# 08_PL_ETH_1.net
KiCad netlist of a schematic drawn in Altium Designer
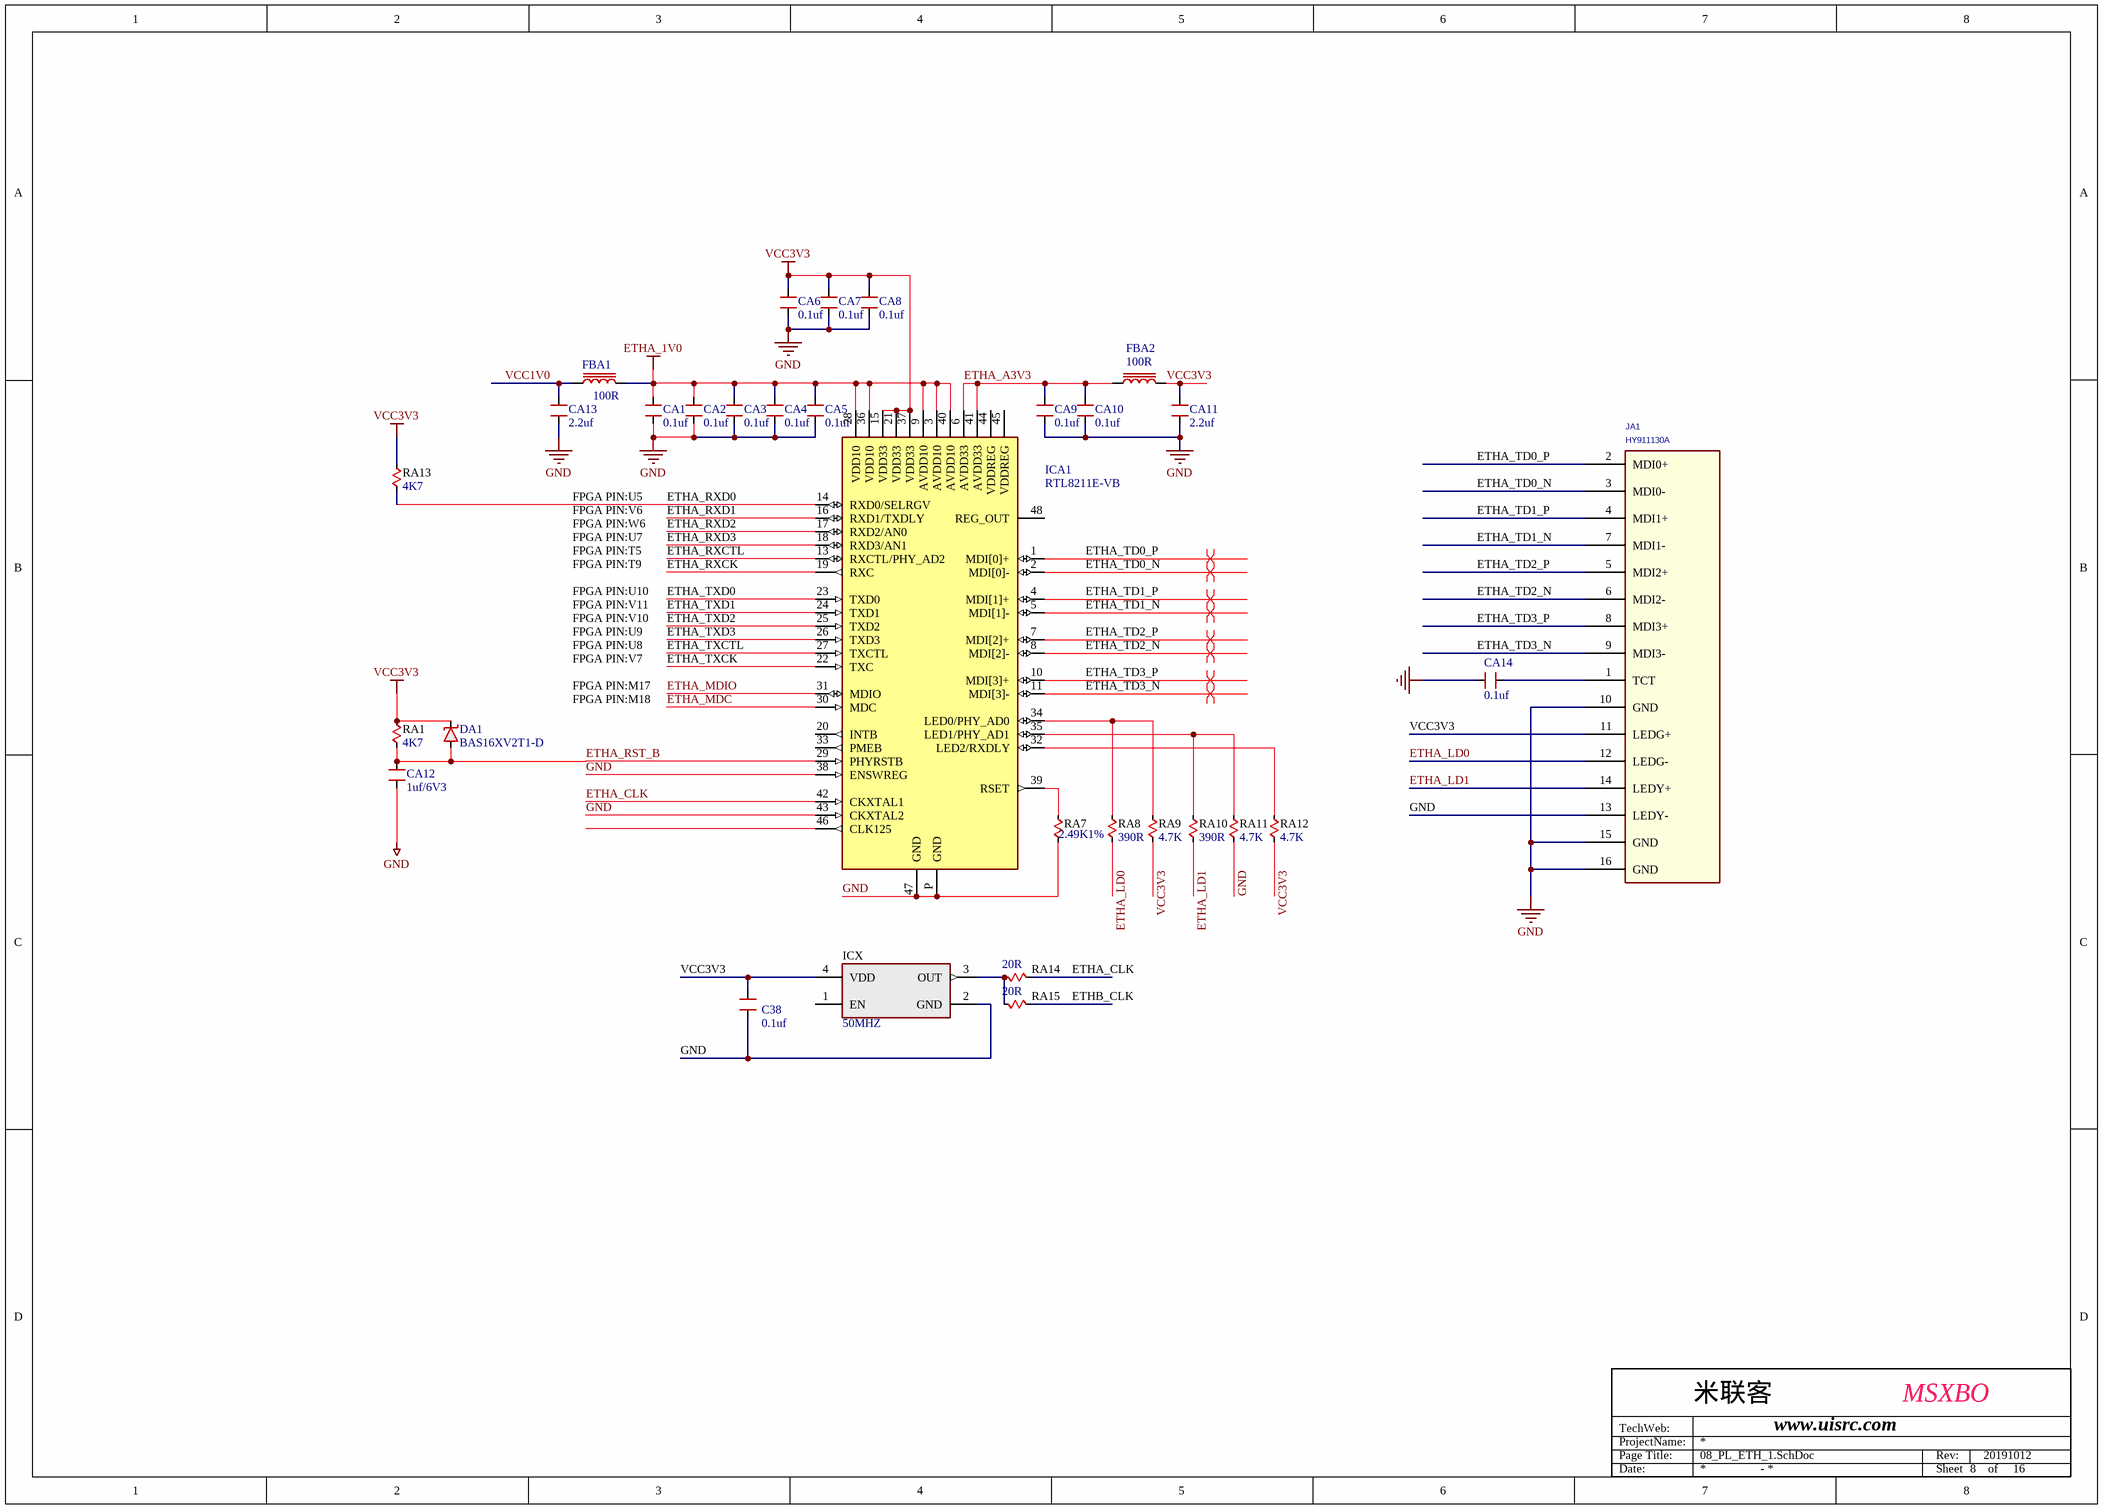
[diagram p0: 08_PL_ETH_1.SchDoc]

(export (version "E")
  (design (tool "Eeschema 10.0.6"))
  (components
    (comp (ref "C38")
      (value "0.1uf")
      (footprint "CAP0402")
      (description "Generic Capacitor")
      (libsource (lib "Digilent") (part "CAPACITOR"))
    )
    (comp (ref "CA1")
      (value "0.1uf")
      (footprint "CAP0402")
      (description "Generic Capacitor")
      (libsource (lib "Miz701_fun20160215") (part "CAPACITOR"))
    )
    (comp (ref "CA2")
      (value "0.1uf")
      (footprint "CAP0402")
      (description "Generic Capacitor")
      (libsource (lib "Miz701_fun20160215") (part "CAPACITOR"))
    )
    (comp (ref "CA3")
      (value "0.1uf")
      (footprint "CAP0402")
      (description "Generic Capacitor")
      (libsource (lib "Miz701_fun20160215") (part "CAPACITOR"))
    )
    (comp (ref "CA4")
      (value "0.1uf")
      (footprint "CAP0402")
      (description "Generic Capacitor")
      (libsource (lib "Miz701_fun20160215") (part "CAPACITOR"))
    )
    (comp (ref "CA5")
      (value "0.1uf")
      (footprint "CAP0402")
      (description "Generic Capacitor")
      (libsource (lib "Miz701_fun20160215") (part "CAPACITOR"))
    )
    (comp (ref "CA6")
      (value "0.1uf")
      (footprint "CAP0402")
      (description "Generic Capacitor")
      (libsource (lib "Miz701_fun20160215") (part "CAPACITOR"))
    )
    (comp (ref "CA7")
      (value "0.1uf")
      (footprint "CAP0402")
      (description "Generic Capacitor")
      (libsource (lib "Miz701_fun20160215") (part "CAPACITOR"))
    )
    (comp (ref "CA8")
      (value "0.1uf")
      (footprint "CAP0402")
      (description "Generic Capacitor")
      (libsource (lib "Miz701_fun20160215") (part "CAPACITOR"))
    )
    (comp (ref "CA9")
      (value "0.1uf")
      (footprint "CAP0402")
      (description "Generic Capacitor")
      (libsource (lib "Miz701_fun20160215") (part "CAPACITOR"))
    )
    (comp (ref "CA10")
      (value "0.1uf")
      (footprint "CAP0402")
      (description "Generic Capacitor")
      (libsource (lib "Miz701_fun20160215") (part "CAPACITOR"))
    )
    (comp (ref "CA11")
      (value "2.2uf")
      (footprint "CAP0402")
      (description "Generic Capacitor")
      (libsource (lib "Miz701_fun20160215") (part "CAPACITOR"))
    )
    (comp (ref "CA12")
      (value "1uf/6V3")
      (footprint "CAP0402")
      (description "Generic Capacitor")
      (fields (field (name "MANUFACTURER") "Murata"))
      (libsource (lib "Miz702N_fun") (part "CAPACITOR"))
    )
    (comp (ref "CA13")
      (value "2.2uf")
      (footprint "CAP0402")
      (description "Generic Capacitor")
      (libsource (lib "Miz701_fun20160215") (part "CAPACITOR"))
    )
    (comp (ref "CA14")
      (value "0.1uf")
      (footprint "CAP0402")
      (description "Generic Capacitor")
      (libsource (lib "Miz701_fun20160215") (part "CAPACITOR"))
    )
    (comp (ref "DA1")
      (value "BAS16XV2T1-D")
      (footprint "SOD-523")
      (description "Surface Mount ESD Protection Diode")
      (fields (field (name "MANUFACTURER") "On Semiconductor"))
      (libsource (lib "Miz702N_fun") (part "DIODE-SCH"))
    )
    (comp (ref "FBA1")
      (value "100R")
      (footprint "CAP0603")
      (description "Generic Ferrite Bead")
      (libsource (lib "Digilent") (part "Ferrite Bead"))
    )
    (comp (ref "FBA2")
      (value "100R")
      (footprint "CAP0603")
      (description "Generic Ferrite Bead")
      (libsource (lib "Digilent") (part "Ferrite Bead"))
    )
    (comp (ref "ICA1")
      (value "RTL8211E-VB")
      (footprint "QFN48")
      (libsource (lib "Miz701_fun20160215") (part "RTL8211E-VL"))
    )
    (comp (ref "ICX")
      (value "50MHZ")
      (footprint "3225")
      (description "3.3V HCMOS Oscillator")
      (fields (field (name "MANUFACTURER") "Fox Electronics"))
      (libsource (lib "Digilent") (part "FXO-HC5"))
    )
    (comp (ref "JA1") (value "HY911130A") (footprint "HY911130A") (libsource (lib "*") (part "HY911130A")))
    (comp (ref "RA1")
      (value "4K7")
      (footprint "RES0402")
      (description "Generic Resistor")
      (libsource (lib "Miz702N_fun") (part "RESISTOR"))
    )
    (comp (ref "RA7")
      (value "2.49K1%")
      (footprint "RES0402")
      (description "Generic Resistor")
      (libsource (lib "Miz701_fun20160215") (part "RESISTOR"))
    )
    (comp (ref "RA8")
      (value "390R")
      (footprint "RES0402")
      (description "Generic Resistor")
      (libsource (lib "Miz701_fun20160215") (part "RESISTOR"))
    )
    (comp (ref "RA9")
      (value "4.7K")
      (footprint "RES0402")
      (description "Generic Resistor")
      (libsource (lib "Miz701_fun20160215") (part "RESISTOR"))
    )
    (comp (ref "RA10")
      (value "390R")
      (footprint "RES0402")
      (description "Generic Resistor")
      (libsource (lib "Miz701_fun20160215") (part "RESISTOR"))
    )
    (comp (ref "RA11")
      (value "4.7K")
      (footprint "RES0402")
      (description "Generic Resistor")
      (libsource (lib "Miz701_fun20160215") (part "RESISTOR"))
    )
    (comp (ref "RA12")
      (value "4.7K")
      (footprint "RES0402")
      (description "Generic Resistor")
      (libsource (lib "Miz701_fun20160215") (part "RESISTOR"))
    )
    (comp (ref "RA13")
      (value "4K7")
      (footprint "RES0402")
      (description "Generic Resistor")
      (libsource (lib "Miz702N_fun") (part "RESISTOR"))
    )
    (comp (ref "RA14")
      (value "20R")
      (footprint "RES0402")
      (description "Generic Resistor")
      (libsource (lib "Digilent") (part "RESISTOR"))
    )
    (comp (ref "RA15")
      (value "20R")
      (footprint "RES0402")
      (description "Generic Resistor")
      (libsource (lib "Digilent") (part "RESISTOR"))
    )
  )
  (nets
    (net (code "1") (name "/ETHA_A3V3") (class "Default")
      (node (ref "CA10") (pin "1") (pinfunction "1_1") (pintype "passive"))
      (node (ref "CA9") (pin "1") (pinfunction "1_1") (pintype "passive"))
      (node (ref "FBA2") (pin "1") (pinfunction "1_1") (pintype "passive"))
      (node (ref "ICA1") (pin "41") (pinfunction "AVDD33_41") (pintype "power_in"))
      (node (ref "ICA1") (pin "6") (pinfunction "AVDD33_6") (pintype "power_in"))
    )
    (net (code "2") (name "/ETHA_CLK") (class "Default")
      (node (ref "ICA1") (pin "42") (pinfunction "CKXTAL1_42") (pintype "input"))
      (node (ref "RA14") (pin "2") (pinfunction "2_2") (pintype "passive"))
    )
    (net (code "3") (name "/ETHA_LD0") (class "Default")
      (node (ref "JA1") (pin "12") (pinfunction "LEDG-_12") (pintype "passive"))
      (node (ref "RA8") (pin "2") (pinfunction "2_2") (pintype "passive"))
    )
    (net (code "4") (name "/ETHA_LD1") (class "Default")
      (node (ref "JA1") (pin "14") (pinfunction "LEDY+_14") (pintype "passive"))
      (node (ref "RA10") (pin "2") (pinfunction "2_2") (pintype "passive"))
    )
    (net (code "5") (name "/ETHA_MDC") (class "Default")
      (node (ref "ICA1") (pin "30") (pinfunction "MDC_30") (pintype "input"))
    )
    (net (code "6") (name "/ETHA_MDIO") (class "Default")
      (node (ref "ICA1") (pin "31") (pinfunction "MDIO_31") (pintype "bidirectional"))
    )
    (net (code "7") (name "/ETHA_RST_B") (class "Default")
      (node (ref "CA12") (pin "1") (pinfunction "1_1") (pintype "passive"))
      (node (ref "DA1") (pin "A") (pinfunction "A_A") (pintype "passive"))
      (node (ref "ICA1") (pin "29") (pinfunction "PHYRSTB_29") (pintype "input"))
      (node (ref "RA1") (pin "2") (pinfunction "2_2") (pintype "passive"))
    )
    (net (code "8") (name "/ETHA_RXCK") (class "Default")
      (node (ref "ICA1") (pin "19") (pinfunction "RXC_19") (pintype "output"))
    )
    (net (code "9") (name "/ETHA_RXCTL") (class "Default")
      (node (ref "ICA1") (pin "13") (pinfunction "RXCTL/PHY_AD2_13") (pintype "bidirectional"))
    )
    (net (code "10") (name "/ETHA_RXD0") (class "Default")
      (node (ref "ICA1") (pin "14") (pinfunction "RXD0/SELRGV_14") (pintype "bidirectional"))
      (node (ref "RA13") (pin "2") (pinfunction "2_2") (pintype "passive"))
    )
    (net (code "11") (name "/ETHA_RXD1") (class "Default")
      (node (ref "ICA1") (pin "16") (pinfunction "RXD1/TXDLY_16") (pintype "bidirectional"))
    )
    (net (code "12") (name "/ETHA_RXD2") (class "Default")
      (node (ref "ICA1") (pin "17") (pinfunction "RXD2/AN0_17") (pintype "bidirectional"))
    )
    (net (code "13") (name "/ETHA_RXD3") (class "Default")
      (node (ref "ICA1") (pin "18") (pinfunction "RXD3/AN1_18") (pintype "bidirectional"))
    )
    (net (code "14") (name "/ETHA_TD0_N") (class "Default")
      (node (ref "ICA1") (pin "2") (pinfunction "MDI[0]-_2") (pintype "bidirectional"))
      (node (ref "JA1") (pin "3") (pinfunction "MDI0-_3") (pintype "passive"))
    )
    (net (code "15") (name "/ETHA_TD0_P") (class "Default")
      (node (ref "ICA1") (pin "1") (pinfunction "MDI[0]+_1") (pintype "bidirectional"))
      (node (ref "JA1") (pin "2") (pinfunction "MDI0+_2") (pintype "passive"))
    )
    (net (code "16") (name "/ETHA_TD1_N") (class "Default")
      (node (ref "ICA1") (pin "5") (pinfunction "MDI[1]-_5") (pintype "bidirectional"))
      (node (ref "JA1") (pin "7") (pinfunction "MDI1-_7") (pintype "passive"))
    )
    (net (code "17") (name "/ETHA_TD1_P") (class "Default")
      (node (ref "ICA1") (pin "4") (pinfunction "MDI[1]+_4") (pintype "bidirectional"))
      (node (ref "JA1") (pin "4") (pinfunction "MDI1+_4") (pintype "passive"))
    )
    (net (code "18") (name "/ETHA_TD2_N") (class "Default")
      (node (ref "ICA1") (pin "8") (pinfunction "MDI[2]-_8") (pintype "bidirectional"))
      (node (ref "JA1") (pin "6") (pinfunction "MDI2-_6") (pintype "passive"))
    )
    (net (code "19") (name "/ETHA_TD2_P") (class "Default")
      (node (ref "ICA1") (pin "7") (pinfunction "MDI[2]+_7") (pintype "bidirectional"))
      (node (ref "JA1") (pin "5") (pinfunction "MDI2+_5") (pintype "passive"))
    )
    (net (code "20") (name "/ETHA_TD3_N") (class "Default")
      (node (ref "ICA1") (pin "11") (pinfunction "MDI[3]-_11") (pintype "bidirectional"))
      (node (ref "JA1") (pin "9") (pinfunction "MDI3-_9") (pintype "passive"))
    )
    (net (code "21") (name "/ETHA_TD3_P") (class "Default")
      (node (ref "ICA1") (pin "10") (pinfunction "MDI[3]+_10") (pintype "bidirectional"))
      (node (ref "JA1") (pin "8") (pinfunction "MDI3+_8") (pintype "passive"))
    )
    (net (code "22") (name "/ETHA_TXCK") (class "Default")
      (node (ref "ICA1") (pin "22") (pinfunction "TXC_22") (pintype "input"))
    )
    (net (code "23") (name "/ETHA_TXCTL") (class "Default")
      (node (ref "ICA1") (pin "27") (pinfunction "TXCTL_27") (pintype "input"))
    )
    (net (code "24") (name "/ETHA_TXD0") (class "Default")
      (node (ref "ICA1") (pin "23") (pinfunction "TXD0_23") (pintype "input"))
    )
    (net (code "25") (name "/ETHA_TXD1") (class "Default")
      (node (ref "ICA1") (pin "24") (pinfunction "TXD1_24") (pintype "input"))
    )
    (net (code "26") (name "/ETHA_TXD2") (class "Default")
      (node (ref "ICA1") (pin "25") (pinfunction "TXD2_25") (pintype "input"))
    )
    (net (code "27") (name "/ETHA_TXD3") (class "Default")
      (node (ref "ICA1") (pin "26") (pinfunction "TXD3_26") (pintype "input"))
    )
    (net (code "28") (name "/ETHB_CLK") (class "Default")
      (node (ref "RA15") (pin "2") (pinfunction "2_2") (pintype "passive"))
    )
    (net (code "29") (name "/VCC1V0") (class "Default")
      (node (ref "CA13") (pin "1") (pinfunction "1_1") (pintype "passive"))
      (node (ref "FBA1") (pin "1") (pinfunction "1_1") (pintype "passive"))
    )
    (net (code "30") (name "ETHA_1V0") (class "Default")
      (node (ref "CA1") (pin "1") (pinfunction "1_1") (pintype "passive"))
      (node (ref "CA2") (pin "1") (pinfunction "1_1") (pintype "passive"))
      (node (ref "CA3") (pin "1") (pinfunction "1_1") (pintype "passive"))
      (node (ref "CA4") (pin "1") (pinfunction "1_1") (pintype "passive"))
      (node (ref "CA5") (pin "1") (pinfunction "1_1") (pintype "passive"))
      (node (ref "FBA1") (pin "2") (pinfunction "2_2") (pintype "passive"))
      (node (ref "ICA1") (pin "28") (pinfunction "VDD10_28") (pintype "power_in"))
      (node (ref "ICA1") (pin "3") (pinfunction "AVDD10_3") (pintype "power_in"))
      (node (ref "ICA1") (pin "36") (pinfunction "VDD10_36") (pintype "power_in"))
      (node (ref "ICA1") (pin "40") (pinfunction "AVDD10_40") (pintype "power_in"))
      (node (ref "ICA1") (pin "9") (pinfunction "AVDD10_9") (pintype "power_in"))
    )
    (net (code "31") (name "GND") (class "Default")
      (node (ref "C38") (pin "2") (pinfunction "2_2") (pintype "passive"))
      (node (ref "CA1") (pin "2") (pinfunction "2_2") (pintype "passive"))
      (node (ref "CA10") (pin "2") (pinfunction "2_2") (pintype "passive"))
      (node (ref "CA11") (pin "2") (pinfunction "2_2") (pintype "passive"))
      (node (ref "CA12") (pin "2") (pinfunction "2_2") (pintype "passive"))
      (node (ref "CA13") (pin "2") (pinfunction "2_2") (pintype "passive"))
      (node (ref "CA14") (pin "1") (pinfunction "1_1") (pintype "passive"))
      (node (ref "CA2") (pin "2") (pinfunction "2_2") (pintype "passive"))
      (node (ref "CA3") (pin "2") (pinfunction "2_2") (pintype "passive"))
      (node (ref "CA4") (pin "2") (pinfunction "2_2") (pintype "passive"))
      (node (ref "CA5") (pin "2") (pinfunction "2_2") (pintype "passive"))
      (node (ref "CA6") (pin "2") (pinfunction "2_2") (pintype "passive"))
      (node (ref "CA7") (pin "2") (pinfunction "2_2") (pintype "passive"))
      (node (ref "CA8") (pin "2") (pinfunction "2_2") (pintype "passive"))
      (node (ref "CA9") (pin "2") (pinfunction "2_2") (pintype "passive"))
      (node (ref "ICA1") (pin "38") (pinfunction "ENSWREG_38") (pintype "input"))
      (node (ref "ICA1") (pin "43") (pinfunction "CKXTAL2_43") (pintype "input"))
      (node (ref "ICA1") (pin "47") (pinfunction "GND_47") (pintype "power_in"))
      (node (ref "ICA1") (pin "P") (pinfunction "GND_P") (pintype "power_in"))
      (node (ref "ICX") (pin "2") (pinfunction "GND_2") (pintype "power_in"))
      (node (ref "JA1") (pin "10") (pinfunction "GND_10") (pintype "power_in"))
      (node (ref "JA1") (pin "13") (pinfunction "LEDY-_13") (pintype "passive"))
      (node (ref "JA1") (pin "15") (pinfunction "GND_15") (pintype "power_in"))
      (node (ref "JA1") (pin "16") (pinfunction "GND_16") (pintype "power_in"))
      (node (ref "RA11") (pin "2") (pinfunction "2_2") (pintype "passive"))
      (node (ref "RA7") (pin "2") (pinfunction "2_2") (pintype "passive"))
    )
    (net (code "32") (name "Net-(ICA1-LED0{slash}PHY_AD0)") (class "Default")
      (node (ref "ICA1") (pin "34") (pinfunction "LED0/PHY_AD0_34") (pintype "bidirectional"))
      (node (ref "RA8") (pin "1") (pinfunction "1_1") (pintype "passive"))
      (node (ref "RA9") (pin "1") (pinfunction "1_1") (pintype "passive"))
    )
    (net (code "33") (name "Net-(ICA1-LED1{slash}PHY_AD1)") (class "Default")
      (node (ref "ICA1") (pin "35") (pinfunction "LED1/PHY_AD1_35") (pintype "bidirectional"))
      (node (ref "RA10") (pin "1") (pinfunction "1_1") (pintype "passive"))
      (node (ref "RA11") (pin "1") (pinfunction "1_1") (pintype "passive"))
    )
    (net (code "34") (name "Net-(ICA1-LED2{slash}RXDLY)") (class "Default")
      (node (ref "ICA1") (pin "32") (pinfunction "LED2/RXDLY_32") (pintype "bidirectional"))
      (node (ref "RA12") (pin "1") (pinfunction "1_1") (pintype "passive"))
    )
    (net (code "35") (name "Net-(ICA1-RSET)") (class "Default")
      (node (ref "ICA1") (pin "39") (pinfunction "RSET_39") (pintype "output"))
      (node (ref "RA7") (pin "1") (pinfunction "1_1") (pintype "passive"))
    )
    (net (code "36") (name "Net-(ICX-OUT)") (class "Default")
      (node (ref "ICX") (pin "3") (pinfunction "OUT_3") (pintype "output"))
      (node (ref "RA14") (pin "1") (pinfunction "1_1") (pintype "passive"))
      (node (ref "RA15") (pin "1") (pinfunction "1_1") (pintype "passive"))
    )
    (net (code "37") (name "Net-(JA1-TCT)") (class "Default")
      (node (ref "CA14") (pin "2") (pinfunction "2_2") (pintype "passive"))
      (node (ref "JA1") (pin "1") (pinfunction "TCT_1") (pintype "passive"))
    )
    (net (code "38") (name "VCC3V3") (class "Default")
      (node (ref "C38") (pin "1") (pinfunction "1_1") (pintype "passive"))
      (node (ref "CA11") (pin "1") (pinfunction "1_1") (pintype "passive"))
      (node (ref "CA6") (pin "1") (pinfunction "1_1") (pintype "passive"))
      (node (ref "CA7") (pin "1") (pinfunction "1_1") (pintype "passive"))
      (node (ref "CA8") (pin "1") (pinfunction "1_1") (pintype "passive"))
      (node (ref "DA1") (pin "K") (pinfunction "K_K") (pintype "passive"))
      (node (ref "FBA2") (pin "2") (pinfunction "2_2") (pintype "passive"))
      (node (ref "ICA1") (pin "15") (pinfunction "VDD33_15") (pintype "power_in"))
      (node (ref "ICA1") (pin "21") (pinfunction "VDD33_21") (pintype "power_in"))
      (node (ref "ICA1") (pin "37") (pinfunction "VDD33_37") (pintype "power_in"))
      (node (ref "ICX") (pin "4") (pinfunction "VDD_4") (pintype "power_in"))
      (node (ref "JA1") (pin "11") (pinfunction "LEDG+_11") (pintype "passive"))
      (node (ref "RA1") (pin "1") (pinfunction "1_1") (pintype "passive"))
      (node (ref "RA12") (pin "2") (pinfunction "2_2") (pintype "passive"))
      (node (ref "RA13") (pin "1") (pinfunction "1_1") (pintype "passive"))
      (node (ref "RA9") (pin "2") (pinfunction "2_2") (pintype "passive"))
    )
    (net (code "39") (name "unconnected-(ICA1-CLK125-Pad46)") (class "Default")
      (node (ref "ICA1") (pin "46") (pinfunction "CLK125_46") (pintype "output"))
    )
    (net (code "40") (name "unconnected-(ICA1-INTB-Pad20)") (class "Default")
      (node (ref "ICA1") (pin "20") (pinfunction "INTB_20") (pintype "output"))
    )
    (net (code "41") (name "unconnected-(ICA1-PMEB-Pad33)") (class "Default")
      (node (ref "ICA1") (pin "33") (pinfunction "PMEB_33") (pintype "output"))
    )
    (net (code "42") (name "unconnected-(ICA1-REG_OUT-Pad48)") (class "Default")
      (node (ref "ICA1") (pin "48") (pinfunction "REG_OUT_48") (pintype "power_in"))
    )
    (net (code "43") (name "unconnected-(ICA1-VDDREG-Pad44)") (class "Default")
      (node (ref "ICA1") (pin "44") (pinfunction "VDDREG_44") (pintype "power_in"))
    )
    (net (code "44") (name "unconnected-(ICA1-VDDREG-Pad45)") (class "Default")
      (node (ref "ICA1") (pin "45") (pinfunction "VDDREG_45") (pintype "power_in"))
    )
    (net (code "45") (name "unconnected-(ICX-EN-Pad1)") (class "Default")
      (node (ref "ICX") (pin "1") (pinfunction "EN_1") (pintype "passive"))
    )
  )
)
